# Motorsteuerung.net
KiCad netlist of a schematic drawn in EAGLE
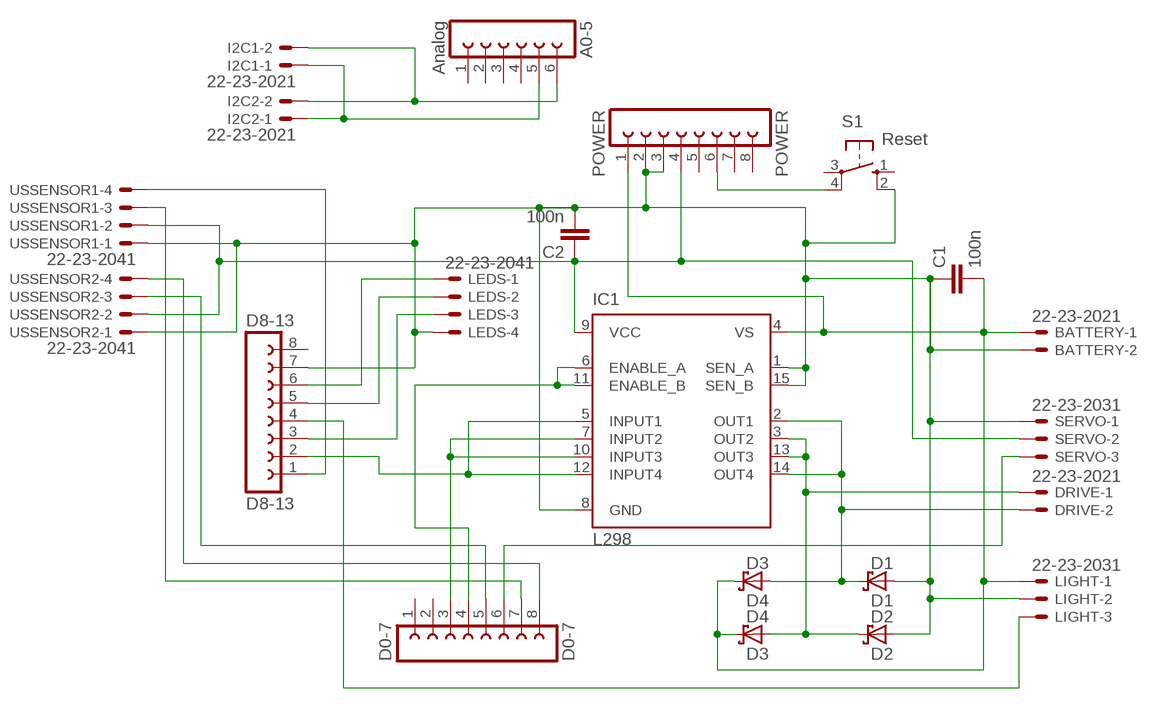
[diagram p0: schematic, sheet 1]

(export (version "E")
  (design (tool "Eeschema 10.0.6"))
  (components
    (comp (ref "A0-5")
      (value "Analog")
      (footprint "eagle-import:FE06")
      (libsource (lib "eagle-import") (part "FE06-1"))
    )
    (comp (ref "BATTERY")
      (value "22-23-2021")
      (footprint "eagle-import:22-23-2021")
      (fields (field (name "MF") "MOLEX"))
      (libsource (lib "eagle-import") (part "22-23-2021"))
    )
    (comp (ref "C1")
      (value "100n")
      (footprint "eagle-import:C025-030X050")
      (libsource (lib "eagle-import") (part "C-EU025-030X050"))
    )
    (comp (ref "C2")
      (value "100n")
      (footprint "eagle-import:C025-030X050")
      (libsource (lib "eagle-import") (part "C-EU025-030X050"))
    )
    (comp (ref "D0-7")
      (value "D0-7")
      (footprint "eagle-import:FE08")
      (libsource (lib "eagle-import") (part "FE08-1"))
    )
    (comp (ref "D1")
      (value "D1")
      (footprint "eagle-import:DO201T15")
      (libsource (lib "eagle-import") (part "SCHOTTKY-DIODEDO201T15"))
    )
    (comp (ref "D2")
      (value "D2")
      (footprint "eagle-import:DO201T15")
      (libsource (lib "eagle-import") (part "SCHOTTKY-DIODEDO201T15"))
    )
    (comp (ref "D3")
      (value "D4")
      (footprint "eagle-import:DO201T15")
      (libsource (lib "eagle-import") (part "SCHOTTKY-DIODEDO201T15"))
    )
    (comp (ref "D4")
      (value "D3")
      (footprint "eagle-import:DO201T15")
      (libsource (lib "eagle-import") (part "SCHOTTKY-DIODEDO201T15"))
    )
    (comp (ref "D8-13")
      (value "D8-13")
      (footprint "eagle-import:FE08")
      (libsource (lib "eagle-import") (part "FE08-1"))
    )
    (comp (ref "DRIVE")
      (value "22-23-2021")
      (footprint "eagle-import:22-23-2021")
      (fields (field (name "MF") "MOLEX"))
      (libsource (lib "eagle-import") (part "22-23-2021"))
    )
    (comp (ref "I2C1")
      (value "22-23-2021")
      (footprint "eagle-import:22-23-2021")
      (fields (field (name "MF") "MOLEX"))
      (libsource (lib "eagle-import") (part "22-23-2021"))
    )
    (comp (ref "I2C2")
      (value "22-23-2021")
      (footprint "eagle-import:22-23-2021")
      (fields
        (field (name "MF") "MOLEX")
        (field (name "MF_1") "MOLEX")
        (field (name "MPN") "22-23-2021")
        (field (name "OC_FARNELL") "1462926")
        (field (name "OC_NEWARK") "25C3832")
      )
      (libsource (lib "eagle-import") (part "22-23-2021"))
    )
    (comp (ref "IC1")
      (value "L298")
      (footprint "eagle-import:MULTIWATT-15")
      (fields (field (name "MPN") "L298N"))
      (libsource (lib "eagle-import") (part "L298"))
    )
    (comp (ref "LEDS")
      (value "22-23-2041")
      (footprint "eagle-import:22-23-2041")
      (fields (field (name "MF") "MOLEX"))
      (libsource (lib "eagle-import") (part "22-23-2041"))
    )
    (comp (ref "LIGHT")
      (value "22-23-2031")
      (footprint "eagle-import:22-23-2031")
      (fields (field (name "MF") "MOLEX"))
      (libsource (lib "eagle-import") (part "22-23-2031"))
    )
    (comp (ref "POWER")
      (value "POWER")
      (footprint "eagle-import:FE08")
      (libsource (lib "eagle-import") (part "FE08-1"))
    )
    (comp (ref "S1")
      (value "Reset")
      (footprint "eagle-import:B3F-10XX")
      (fields (field (name "MPN") "B3F-1000"))
      (libsource (lib "eagle-import") (part "10-XX"))
    )
    (comp (ref "SERVO")
      (value "22-23-2031")
      (footprint "eagle-import:22-23-2031")
      (fields (field (name "MF") "MOLEX"))
      (libsource (lib "eagle-import") (part "22-23-2031"))
    )
    (comp (ref "USSENSOR1")
      (value "22-23-2041")
      (footprint "eagle-import:22-23-2041")
      (fields
        (field (name "MF") "MOLEX")
        (field (name "MPN") "22-23-2041")
        (field (name "OC_FARNELL") "1462920")
        (field (name "OC_NEWARK") "38C0355")
      )
      (libsource (lib "eagle-import") (part "22-23-2041"))
    )
    (comp (ref "USSENSOR2")
      (value "22-23-2041")
      (footprint "eagle-import:22-23-2041")
      (fields
        (field (name "MF") "MOLEX")
        (field (name "MF_1") "MOLEX")
        (field (name "MPN") "22-23-2041")
        (field (name "OC_FARNELL") "1462920")
        (field (name "OC_NEWARK") "38C0355")
      )
      (libsource (lib "eagle-import") (part "22-23-2041"))
    )
  )
  (nets
    (net (code "1") (name "Net-(BATTERYA-S)") (class "Default")
      (node (ref "BATTERY") (pin "1") (pinfunction "S_1") (pintype "passive"))
      (node (ref "C1") (pin "2") (pinfunction "2_2") (pintype "passive"))
      (node (ref "D3") (pin "C") (pinfunction "C_C") (pintype "passive"))
      (node (ref "D4") (pin "C") (pinfunction "C_C") (pintype "passive"))
      (node (ref "IC1") (pin "4") (pinfunction "VS_4") (pintype "power_in"))
      (node (ref "LIGHT") (pin "1") (pinfunction "S_1") (pintype "passive"))
      (node (ref "POWER") (pin "1") (pinfunction "1_1") (pintype "passive"))
    )
    (net (code "2") (name "Net-(BATTERYB-S)") (class "Default")
      (node (ref "BATTERY") (pin "2") (pinfunction "S_2") (pintype "passive"))
      (node (ref "C1") (pin "1") (pinfunction "1_1") (pintype "passive"))
      (node (ref "C2") (pin "2") (pinfunction "2_2") (pintype "passive"))
      (node (ref "D1") (pin "A") (pinfunction "A_A") (pintype "passive"))
      (node (ref "D2") (pin "A") (pinfunction "A_A") (pintype "passive"))
      (node (ref "D8-13") (pin "7") (pinfunction "7_7") (pintype "passive"))
      (node (ref "IC1") (pin "1") (pinfunction "SEN_A_1") (pintype "input"))
      (node (ref "IC1") (pin "15") (pinfunction "SEN_B_15") (pintype "input"))
      (node (ref "IC1") (pin "8") (pinfunction "GND_8") (pintype "power_in"))
      (node (ref "LEDS") (pin "4") (pinfunction "S_4") (pintype "passive"))
      (node (ref "LIGHT") (pin "2") (pinfunction "S_2") (pintype "passive"))
      (node (ref "POWER") (pin "2") (pinfunction "2_2") (pintype "passive"))
      (node (ref "POWER") (pin "3") (pinfunction "3_3") (pintype "passive"))
      (node (ref "S1") (pin "2") (pinfunction "S1_2") (pintype "passive"))
      (node (ref "SERVO") (pin "1") (pinfunction "S_1") (pintype "passive"))
      (node (ref "USSENSOR1") (pin "1") (pinfunction "S_1") (pintype "passive"))
      (node (ref "USSENSOR2") (pin "1") (pinfunction "S_1") (pintype "passive"))
    )
    (net (code "3") (name "Net-(DRIVEA-S)") (class "Default")
      (node (ref "D2") (pin "C") (pinfunction "C_C") (pintype "passive"))
      (node (ref "D3") (pin "A") (pinfunction "A_A") (pintype "passive"))
      (node (ref "DRIVE") (pin "1") (pinfunction "S_1") (pintype "passive"))
      (node (ref "IC1") (pin "13") (pinfunction "OUT3_13") (pintype "output"))
      (node (ref "IC1") (pin "3") (pinfunction "OUT2_3") (pintype "output"))
    )
    (net (code "4") (name "Net-(DRIVEB-S)") (class "Default")
      (node (ref "D1") (pin "C") (pinfunction "C_C") (pintype "passive"))
      (node (ref "D4") (pin "A") (pinfunction "A_A") (pintype "passive"))
      (node (ref "DRIVE") (pin "2") (pinfunction "S_2") (pintype "passive"))
      (node (ref "IC1") (pin "14") (pinfunction "OUT4_14") (pintype "output"))
      (node (ref "IC1") (pin "2") (pinfunction "OUT1_2") (pintype "output"))
    )
    (net (code "5") (name "Net-(I2C1A-S)") (class "Default")
      (node (ref "A0-5") (pin "5") (pinfunction "5_5") (pintype "passive"))
      (node (ref "I2C1") (pin "1") (pinfunction "S_1") (pintype "passive"))
      (node (ref "I2C2") (pin "1") (pinfunction "S_1") (pintype "passive"))
    )
    (net (code "6") (name "Net-(I2C1B-S)") (class "Default")
      (node (ref "A0-5") (pin "6") (pinfunction "6_6") (pintype "passive"))
      (node (ref "I2C1") (pin "2") (pinfunction "S_2") (pintype "passive"))
      (node (ref "I2C2") (pin "2") (pinfunction "S_2") (pintype "passive"))
    )
    (net (code "7") (name "Net-(IC1-ENABLE_A)") (class "Default")
      (node (ref "D0-7") (pin "4") (pinfunction "4_4") (pintype "passive"))
      (node (ref "IC1") (pin "11") (pinfunction "ENABLE_B_11") (pintype "input"))
      (node (ref "IC1") (pin "6") (pinfunction "ENABLE_A_6") (pintype "input"))
    )
    (net (code "8") (name "Net-(IC1-INPUT1)") (class "Default")
      (node (ref "D8-13") (pin "2") (pinfunction "2_2") (pintype "passive"))
      (node (ref "IC1") (pin "12") (pinfunction "INPUT4_12") (pintype "input"))
      (node (ref "IC1") (pin "5") (pinfunction "INPUT1_5") (pintype "input"))
    )
    (net (code "9") (name "Net-(IC1-INPUT2)") (class "Default")
      (node (ref "D0-7") (pin "3") (pinfunction "3_3") (pintype "passive"))
      (node (ref "IC1") (pin "10") (pinfunction "INPUT3_10") (pintype "input"))
      (node (ref "IC1") (pin "7") (pinfunction "INPUT2_7") (pintype "input"))
    )
    (net (code "10") (name "Net-(IC1-VCC)") (class "Default")
      (node (ref "C2") (pin "1") (pinfunction "1_1") (pintype "passive"))
      (node (ref "IC1") (pin "9") (pinfunction "VCC_9") (pintype "power_in"))
      (node (ref "POWER") (pin "4") (pinfunction "4_4") (pintype "passive"))
      (node (ref "SERVO") (pin "2") (pinfunction "S_2") (pintype "passive"))
      (node (ref "USSENSOR1") (pin "2") (pinfunction "S_2") (pintype "passive"))
      (node (ref "USSENSOR2") (pin "2") (pinfunction "S_2") (pintype "passive"))
    )
    (net (code "11") (name "Net-(LEDSA-S)") (class "Default")
      (node (ref "D8-13") (pin "6") (pinfunction "6_6") (pintype "passive"))
      (node (ref "LEDS") (pin "1") (pinfunction "S_1") (pintype "passive"))
    )
    (net (code "12") (name "Net-(LEDSB-S)") (class "Default")
      (node (ref "D8-13") (pin "5") (pinfunction "5_5") (pintype "passive"))
      (node (ref "LEDS") (pin "2") (pinfunction "S_2") (pintype "passive"))
    )
    (net (code "13") (name "Net-(LEDSC-S)") (class "Default")
      (node (ref "D8-13") (pin "3") (pinfunction "3_3") (pintype "passive"))
      (node (ref "LEDS") (pin "3") (pinfunction "S_3") (pintype "passive"))
    )
    (net (code "14") (name "Net-(LIGHTC-S)") (class "Default")
      (node (ref "D8-13") (pin "4") (pinfunction "4_4") (pintype "passive"))
      (node (ref "LIGHT") (pin "3") (pinfunction "S_3") (pintype "passive"))
    )
    (net (code "15") (name "Net-(S1-P1)") (class "Default")
      (node (ref "POWER") (pin "6") (pinfunction "6_6") (pintype "passive"))
      (node (ref "S1") (pin "4") (pinfunction "P1_4") (pintype "passive"))
    )
    (net (code "16") (name "Net-(SERVOC-S)") (class "Default")
      (node (ref "D0-7") (pin "6") (pinfunction "6_6") (pintype "passive"))
      (node (ref "SERVO") (pin "3") (pinfunction "S_3") (pintype "passive"))
    )
    (net (code "17") (name "Net-(USSENSOR1C-S)") (class "Default")
      (node (ref "D0-7") (pin "7") (pinfunction "7_7") (pintype "passive"))
      (node (ref "USSENSOR1") (pin "3") (pinfunction "S_3") (pintype "passive"))
    )
    (net (code "18") (name "Net-(USSENSOR1D-S)") (class "Default")
      (node (ref "D8-13") (pin "1") (pinfunction "1_1") (pintype "passive"))
      (node (ref "USSENSOR1") (pin "4") (pinfunction "S_4") (pintype "passive"))
    )
    (net (code "19") (name "Net-(USSENSOR2C-S)") (class "Default")
      (node (ref "D0-7") (pin "5") (pinfunction "5_5") (pintype "passive"))
      (node (ref "USSENSOR2") (pin "3") (pinfunction "S_3") (pintype "passive"))
    )
    (net (code "20") (name "Net-(USSENSOR2D-S)") (class "Default")
      (node (ref "D0-7") (pin "8") (pinfunction "8_8") (pintype "passive"))
      (node (ref "USSENSOR2") (pin "4") (pinfunction "S_4") (pintype "passive"))
    )
    (net (code "21") (name "unconnected-(A0-5-Pad1)") (class "Default")
      (node (ref "A0-5") (pin "1") (pinfunction "1_1") (pintype "passive"))
    )
    (net (code "22") (name "unconnected-(A0-5-Pad2)") (class "Default")
      (node (ref "A0-5") (pin "2") (pinfunction "2_2") (pintype "passive"))
    )
    (net (code "23") (name "unconnected-(A0-5-Pad3)") (class "Default")
      (node (ref "A0-5") (pin "3") (pinfunction "3_3") (pintype "passive"))
    )
    (net (code "24") (name "unconnected-(A0-5-Pad4)") (class "Default")
      (node (ref "A0-5") (pin "4") (pinfunction "4_4") (pintype "passive"))
    )
    (net (code "25") (name "unconnected-(D0-7-Pad1)") (class "Default")
      (node (ref "D0-7") (pin "1") (pinfunction "1_1") (pintype "passive"))
    )
    (net (code "26") (name "unconnected-(D0-7-Pad2)") (class "Default")
      (node (ref "D0-7") (pin "2") (pinfunction "2_2") (pintype "passive"))
    )
    (net (code "27") (name "unconnected-(D8-13-Pad8)") (class "Default")
      (node (ref "D8-13") (pin "8") (pinfunction "8_8") (pintype "passive"))
    )
    (net (code "28") (name "unconnected-(POWER-Pad5)") (class "Default")
      (node (ref "POWER") (pin "5") (pinfunction "5_5") (pintype "passive"))
    )
    (net (code "29") (name "unconnected-(POWER-Pad7)") (class "Default")
      (node (ref "POWER") (pin "7") (pinfunction "7_7") (pintype "passive"))
    )
    (net (code "30") (name "unconnected-(POWER-Pad8)") (class "Default")
      (node (ref "POWER") (pin "8") (pinfunction "8_8") (pintype "passive"))
    )
    (net (code "31") (name "unconnected-(S1-P-Pad3)") (class "Default")
      (node (ref "S1") (pin "3") (pinfunction "P_3") (pintype "passive"))
    )
    (net (code "32") (name "unconnected-(S1-S-Pad1)") (class "Default")
      (node (ref "S1") (pin "1") (pinfunction "S_1") (pintype "passive"))
    )
  )
)
